# hauptplatine.net
KiCad netlist of a schematic drawn in EAGLE
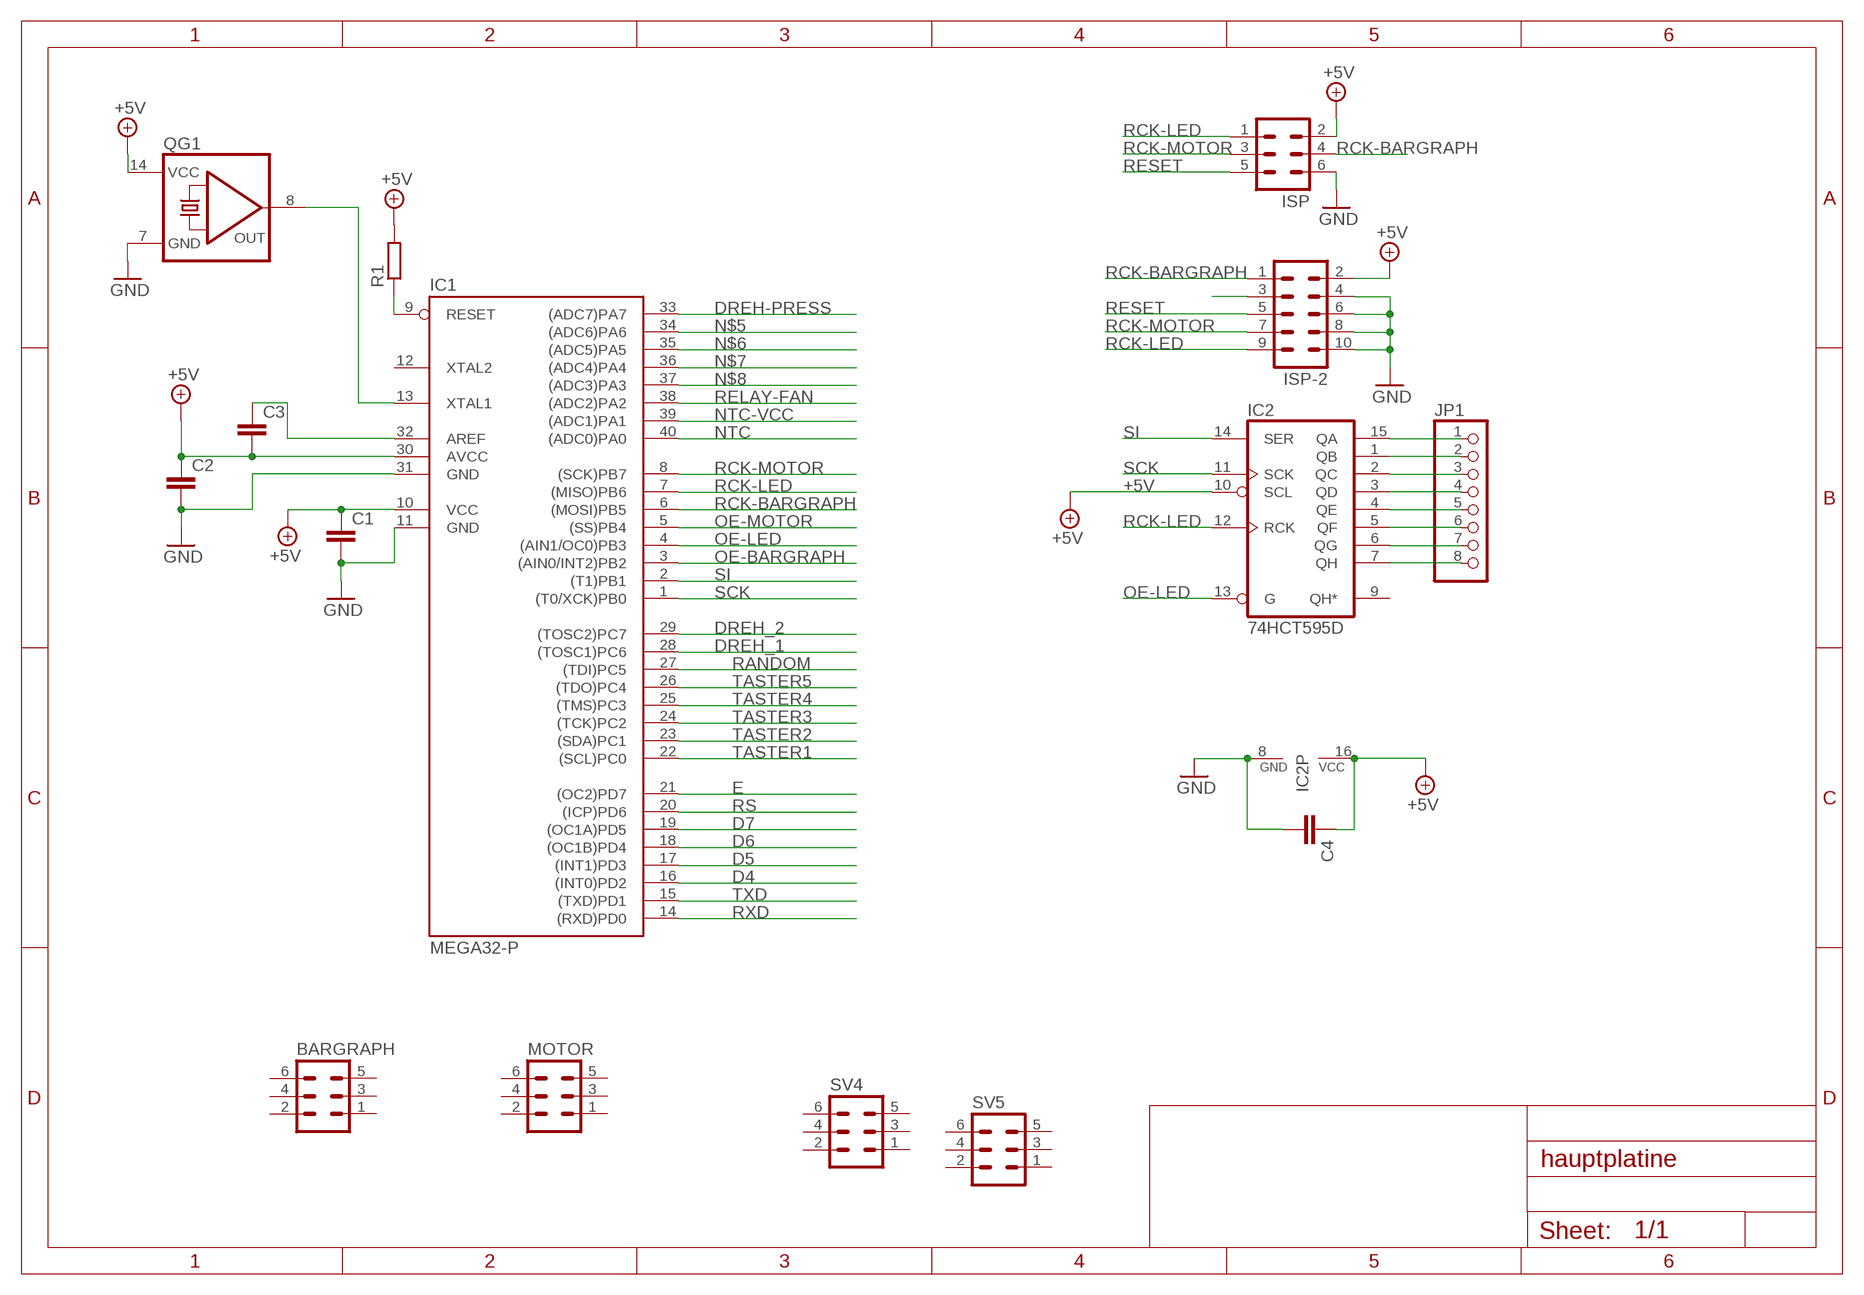
[diagram p0: schematic, sheet 1]

(export (version "E")
  (design (tool "Eeschema 10.0.6"))
  (components
    (comp (ref "BARGRAPH")
      (value "ML6")
      (footprint "eagle-import:ML6")
      (libsource (lib "eagle-import") (part "ML6"))
    )
    (comp (ref "C1")
      (value "C-EU025-025X050")
      (footprint "eagle-import:C025-025X050")
      (libsource (lib "eagle-import") (part "C-EU025-025X050"))
    )
    (comp (ref "C2")
      (value "C-EUC0805")
      (footprint "eagle-import:C0805")
      (libsource (lib "eagle-import") (part "C-EUC0805"))
    )
    (comp (ref "C3")
      (value "C-EUC0805")
      (footprint "eagle-import:C0805")
      (libsource (lib "eagle-import") (part "C-EUC0805"))
    )
    (comp (ref "C4")
      (value "C-EU025-025X050")
      (footprint "eagle-import:C025-025X050")
      (libsource (lib "eagle-import") (part "C-EU025-025X050"))
    )
    (comp (ref "IC1")
      (value "MEGA32-P")
      (footprint "eagle-import:DIL40")
      (fields (field (name "MPN") "ATMEGA32-16PU"))
      (libsource (lib "eagle-import") (part "MEGA32-P"))
    )
    (comp (ref "IC2")
      (value "74HCT595D")
      (footprint "eagle-import:SO16")
      (libsource (lib "eagle-import") (part "74595DHCT"))
    )
    (comp (ref "ISP")
      (value "ML6")
      (footprint "eagle-import:ML6")
      (libsource (lib "eagle-import") (part "ML6"))
    )
    (comp (ref "ISP-2")
      (value "ML10")
      (footprint "eagle-import:ML10")
      (libsource (lib "eagle-import") (part "ML10"))
    )
    (comp (ref "JP1")
      (value "PINHD-1X8")
      (footprint "eagle-import:1X08")
      (libsource (lib "eagle-import") (part "PINHD-1X8"))
    )
    (comp (ref "MOTOR")
      (value "ML6")
      (footprint "eagle-import:ML6")
      (libsource (lib "eagle-import") (part "ML6"))
    )
    (comp (ref "QG1")
      (value "QG5860")
      (footprint "eagle-import:DIL14S")
      (libsource (lib "eagle-import") (part "QG5860"))
    )
    (comp (ref "R1")
      (value "R-EU_0207/10")
      (footprint "eagle-import:0207_10")
      (libsource (lib "eagle-import") (part "R-EU_0207/10"))
    )
    (comp (ref "SV4")
      (value "ML6")
      (footprint "eagle-import:ML6")
      (libsource (lib "eagle-import") (part "ML6"))
    )
    (comp (ref "SV5")
      (value "ML6")
      (footprint "eagle-import:ML6")
      (libsource (lib "eagle-import") (part "ML6"))
    )
  )
  (nets
    (net (code "1") (name "+5V") (class "Default")
      (node (ref "C1") (pin "1") (pinfunction "1_1") (pintype "passive"))
      (node (ref "C2") (pin "1") (pinfunction "1_1") (pintype "passive"))
      (node (ref "C3") (pin "2") (pinfunction "2_2") (pintype "passive"))
      (node (ref "C4") (pin "1") (pinfunction "1_1") (pintype "passive"))
      (node (ref "IC1") (pin "10") (pinfunction "VCC_10") (pintype "power_in"))
      (node (ref "IC1") (pin "30") (pinfunction "AVCC_30") (pintype "power_in"))
      (node (ref "IC2") (pin "10") (pinfunction "SCL_10") (pintype "input"))
      (node (ref "IC2") (pin "16") (pinfunction "VCC_16") (pintype "power_in"))
      (node (ref "ISP") (pin "2") (pinfunction "2_2") (pintype "passive"))
      (node (ref "ISP-2") (pin "2") (pinfunction "2_2") (pintype "passive"))
      (node (ref "QG1") (pin "14") (pinfunction "VCC_14") (pintype "power_in"))
      (node (ref "R1") (pin "2") (pinfunction "2_2") (pintype "passive"))
    )
    (net (code "2") (name "/D4") (class "Default")
      (node (ref "IC1") (pin "16") (pinfunction "(INT0)PD2_16") (pintype "bidirectional"))
    )
    (net (code "3") (name "/D5") (class "Default")
      (node (ref "IC1") (pin "17") (pinfunction "(INT1)PD3_17") (pintype "bidirectional"))
    )
    (net (code "4") (name "/D6") (class "Default")
      (node (ref "IC1") (pin "18") (pinfunction "(OC1B)PD4_18") (pintype "bidirectional"))
    )
    (net (code "5") (name "/D7") (class "Default")
      (node (ref "IC1") (pin "19") (pinfunction "(OC1A)PD5_19") (pintype "bidirectional"))
    )
    (net (code "6") (name "/DREH-PRESS") (class "Default")
      (node (ref "IC1") (pin "33") (pinfunction "(ADC7)PA7_33") (pintype "bidirectional"))
    )
    (net (code "7") (name "/DREH_1") (class "Default")
      (node (ref "IC1") (pin "28") (pinfunction "(TOSC1)PC6_28") (pintype "bidirectional"))
    )
    (net (code "8") (name "/DREH_2") (class "Default")
      (node (ref "IC1") (pin "29") (pinfunction "(TOSC2)PC7_29") (pintype "bidirectional"))
    )
    (net (code "9") (name "/E") (class "Default")
      (node (ref "IC1") (pin "21") (pinfunction "(OC2)PD7_21") (pintype "bidirectional"))
    )
    (net (code "10") (name "/N$5") (class "Default")
      (node (ref "IC1") (pin "34") (pinfunction "(ADC6)PA6_34") (pintype "bidirectional"))
    )
    (net (code "11") (name "/N$6") (class "Default")
      (node (ref "IC1") (pin "35") (pinfunction "(ADC5)PA5_35") (pintype "bidirectional"))
    )
    (net (code "12") (name "/N$7") (class "Default")
      (node (ref "IC1") (pin "36") (pinfunction "(ADC4)PA4_36") (pintype "bidirectional"))
    )
    (net (code "13") (name "/N$8") (class "Default")
      (node (ref "IC1") (pin "37") (pinfunction "(ADC3)PA3_37") (pintype "bidirectional"))
    )
    (net (code "14") (name "/NTC") (class "Default")
      (node (ref "IC1") (pin "40") (pinfunction "(ADC0)PA0_40") (pintype "bidirectional"))
    )
    (net (code "15") (name "/NTC-VCC") (class "Default")
      (node (ref "IC1") (pin "39") (pinfunction "(ADC1)PA1_39") (pintype "bidirectional"))
    )
    (net (code "16") (name "/OE-BARGRAPH") (class "Default")
      (node (ref "IC1") (pin "3") (pinfunction "(AIN0/INT2)PB2_3") (pintype "bidirectional"))
    )
    (net (code "17") (name "/OE-LED") (class "Default")
      (node (ref "IC1") (pin "4") (pinfunction "(AIN1/OC0)PB3_4") (pintype "bidirectional"))
      (node (ref "IC2") (pin "13") (pinfunction "G_13") (pintype "input"))
    )
    (net (code "18") (name "/OE-MOTOR") (class "Default")
      (node (ref "IC1") (pin "5") (pinfunction "(SS)PB4_5") (pintype "bidirectional"))
    )
    (net (code "19") (name "/RANDOM") (class "Default")
      (node (ref "IC1") (pin "27") (pinfunction "(TDI)PC5_27") (pintype "bidirectional"))
    )
    (net (code "20") (name "/RCK-BARGRAPH") (class "Default")
      (node (ref "IC1") (pin "6") (pinfunction "(MOSI)PB5_6") (pintype "bidirectional"))
      (node (ref "ISP") (pin "4") (pinfunction "4_4") (pintype "passive"))
      (node (ref "ISP-2") (pin "1") (pinfunction "1_1") (pintype "passive"))
    )
    (net (code "21") (name "/RCK-LED") (class "Default")
      (node (ref "IC1") (pin "7") (pinfunction "(MISO)PB6_7") (pintype "bidirectional"))
      (node (ref "IC2") (pin "12") (pinfunction "RCK_12") (pintype "input"))
      (node (ref "ISP") (pin "1") (pinfunction "1_1") (pintype "passive"))
      (node (ref "ISP-2") (pin "9") (pinfunction "9_9") (pintype "passive"))
    )
    (net (code "22") (name "/RCK-MOTOR") (class "Default")
      (node (ref "IC1") (pin "8") (pinfunction "(SCK)PB7_8") (pintype "bidirectional"))
      (node (ref "ISP") (pin "3") (pinfunction "3_3") (pintype "passive"))
      (node (ref "ISP-2") (pin "7") (pinfunction "7_7") (pintype "passive"))
    )
    (net (code "23") (name "/RELAY-FAN") (class "Default")
      (node (ref "IC1") (pin "38") (pinfunction "(ADC2)PA2_38") (pintype "bidirectional"))
    )
    (net (code "24") (name "/RESET") (class "Default")
      (node (ref "IC1") (pin "9") (pinfunction "RESET_9") (pintype "input"))
      (node (ref "ISP") (pin "5") (pinfunction "5_5") (pintype "passive"))
      (node (ref "ISP-2") (pin "5") (pinfunction "5_5") (pintype "passive"))
      (node (ref "R1") (pin "1") (pinfunction "1_1") (pintype "passive"))
    )
    (net (code "25") (name "/RS") (class "Default")
      (node (ref "IC1") (pin "20") (pinfunction "(ICP)PD6_20") (pintype "bidirectional"))
    )
    (net (code "26") (name "/RXD") (class "Default")
      (node (ref "IC1") (pin "14") (pinfunction "(RXD)PD0_14") (pintype "bidirectional"))
    )
    (net (code "27") (name "/SCK") (class "Default")
      (node (ref "IC1") (pin "1") (pinfunction "(T0/XCK)PB0_1") (pintype "bidirectional"))
      (node (ref "IC2") (pin "11") (pinfunction "SCK_11") (pintype "input"))
    )
    (net (code "28") (name "/SI") (class "Default")
      (node (ref "IC1") (pin "2") (pinfunction "(T1)PB1_2") (pintype "bidirectional"))
      (node (ref "IC2") (pin "14") (pinfunction "SER_14") (pintype "input"))
    )
    (net (code "29") (name "/TASTER1") (class "Default")
      (node (ref "IC1") (pin "22") (pinfunction "(SCL)PC0_22") (pintype "bidirectional"))
    )
    (net (code "30") (name "/TASTER2") (class "Default")
      (node (ref "IC1") (pin "23") (pinfunction "(SDA)PC1_23") (pintype "bidirectional"))
    )
    (net (code "31") (name "/TASTER3") (class "Default")
      (node (ref "IC1") (pin "24") (pinfunction "(TCK)PC2_24") (pintype "bidirectional"))
    )
    (net (code "32") (name "/TASTER4") (class "Default")
      (node (ref "IC1") (pin "25") (pinfunction "(TMS)PC3_25") (pintype "bidirectional"))
    )
    (net (code "33") (name "/TASTER5") (class "Default")
      (node (ref "IC1") (pin "26") (pinfunction "(TDO)PC4_26") (pintype "bidirectional"))
    )
    (net (code "34") (name "/TXD") (class "Default")
      (node (ref "IC1") (pin "15") (pinfunction "(TXD)PD1_15") (pintype "bidirectional"))
    )
    (net (code "35") (name "GND") (class "Default")
      (node (ref "C1") (pin "2") (pinfunction "2_2") (pintype "passive"))
      (node (ref "C2") (pin "2") (pinfunction "2_2") (pintype "passive"))
      (node (ref "C4") (pin "2") (pinfunction "2_2") (pintype "passive"))
      (node (ref "IC1") (pin "11") (pinfunction "GND_11") (pintype "power_in"))
      (node (ref "IC1") (pin "31") (pinfunction "GND_31") (pintype "power_in"))
      (node (ref "IC2") (pin "8") (pinfunction "GND_8") (pintype "power_in"))
      (node (ref "ISP") (pin "6") (pinfunction "6_6") (pintype "passive"))
      (node (ref "ISP-2") (pin "10") (pinfunction "10_10") (pintype "passive"))
      (node (ref "ISP-2") (pin "4") (pinfunction "4_4") (pintype "passive"))
      (node (ref "ISP-2") (pin "6") (pinfunction "6_6") (pintype "passive"))
      (node (ref "ISP-2") (pin "8") (pinfunction "8_8") (pintype "passive"))
      (node (ref "QG1") (pin "7") (pinfunction "GND_7") (pintype "power_in"))
    )
    (net (code "36") (name "Net-(IC1-AREF)") (class "Default")
      (node (ref "C3") (pin "1") (pinfunction "1_1") (pintype "passive"))
      (node (ref "IC1") (pin "32") (pinfunction "AREF_32") (pintype "passive"))
    )
    (net (code "37") (name "Net-(IC1-XTAL1)") (class "Default")
      (node (ref "IC1") (pin "13") (pinfunction "XTAL1_13") (pintype "bidirectional"))
      (node (ref "QG1") (pin "8") (pinfunction "OUT_8") (pintype "output"))
    )
    (net (code "38") (name "Net-(IC2A-QA)") (class "Default")
      (node (ref "IC2") (pin "15") (pinfunction "QA_15") (pintype "tri_state"))
      (node (ref "JP1") (pin "1") (pinfunction "1_1") (pintype "passive"))
    )
    (net (code "39") (name "Net-(IC2A-QB)") (class "Default")
      (node (ref "IC2") (pin "1") (pinfunction "QB_1") (pintype "tri_state"))
      (node (ref "JP1") (pin "2") (pinfunction "2_2") (pintype "passive"))
    )
    (net (code "40") (name "Net-(IC2A-QC)") (class "Default")
      (node (ref "IC2") (pin "2") (pinfunction "QC_2") (pintype "tri_state"))
      (node (ref "JP1") (pin "3") (pinfunction "3_3") (pintype "passive"))
    )
    (net (code "41") (name "Net-(IC2A-QD)") (class "Default")
      (node (ref "IC2") (pin "3") (pinfunction "QD_3") (pintype "tri_state"))
      (node (ref "JP1") (pin "4") (pinfunction "4_4") (pintype "passive"))
    )
    (net (code "42") (name "Net-(IC2A-QE)") (class "Default")
      (node (ref "IC2") (pin "4") (pinfunction "QE_4") (pintype "tri_state"))
      (node (ref "JP1") (pin "5") (pinfunction "5_5") (pintype "passive"))
    )
    (net (code "43") (name "Net-(IC2A-QF)") (class "Default")
      (node (ref "IC2") (pin "5") (pinfunction "QF_5") (pintype "tri_state"))
      (node (ref "JP1") (pin "6") (pinfunction "6_6") (pintype "passive"))
    )
    (net (code "44") (name "Net-(IC2A-QG)") (class "Default")
      (node (ref "IC2") (pin "6") (pinfunction "QG_6") (pintype "tri_state"))
      (node (ref "JP1") (pin "7") (pinfunction "7_7") (pintype "passive"))
    )
    (net (code "45") (name "Net-(IC2A-QH)") (class "Default")
      (node (ref "IC2") (pin "7") (pinfunction "QH_7") (pintype "tri_state"))
      (node (ref "JP1") (pin "8") (pinfunction "8_8") (pintype "passive"))
    )
    (net (code "46") (name "unconnected-(BARGRAPH-Pad1)") (class "Default")
      (node (ref "BARGRAPH") (pin "1") (pinfunction "1_1") (pintype "passive"))
    )
    (net (code "47") (name "unconnected-(BARGRAPH-Pad2)") (class "Default")
      (node (ref "BARGRAPH") (pin "2") (pinfunction "2_2") (pintype "passive"))
    )
    (net (code "48") (name "unconnected-(BARGRAPH-Pad3)") (class "Default")
      (node (ref "BARGRAPH") (pin "3") (pinfunction "3_3") (pintype "passive"))
    )
    (net (code "49") (name "unconnected-(BARGRAPH-Pad4)") (class "Default")
      (node (ref "BARGRAPH") (pin "4") (pinfunction "4_4") (pintype "passive"))
    )
    (net (code "50") (name "unconnected-(BARGRAPH-Pad5)") (class "Default")
      (node (ref "BARGRAPH") (pin "5") (pinfunction "5_5") (pintype "passive"))
    )
    (net (code "51") (name "unconnected-(BARGRAPH-Pad6)") (class "Default")
      (node (ref "BARGRAPH") (pin "6") (pinfunction "6_6") (pintype "passive"))
    )
    (net (code "52") (name "unconnected-(IC1-XTAL2-Pad12)") (class "Default")
      (node (ref "IC1") (pin "12") (pinfunction "XTAL2_12") (pintype "bidirectional"))
    )
    (net (code "53") (name "unconnected-(IC2A-QH*-Pad9)") (class "Default")
      (node (ref "IC2") (pin "9") (pinfunction "QH*_9") (pintype "tri_state"))
    )
    (net (code "54") (name "unconnected-(ISP-2-Pad3)") (class "Default")
      (node (ref "ISP-2") (pin "3") (pinfunction "3_3") (pintype "passive"))
    )
    (net (code "55") (name "unconnected-(MOTOR-Pad1)") (class "Default")
      (node (ref "MOTOR") (pin "1") (pinfunction "1_1") (pintype "passive"))
    )
    (net (code "56") (name "unconnected-(MOTOR-Pad2)") (class "Default")
      (node (ref "MOTOR") (pin "2") (pinfunction "2_2") (pintype "passive"))
    )
    (net (code "57") (name "unconnected-(MOTOR-Pad3)") (class "Default")
      (node (ref "MOTOR") (pin "3") (pinfunction "3_3") (pintype "passive"))
    )
    (net (code "58") (name "unconnected-(MOTOR-Pad4)") (class "Default")
      (node (ref "MOTOR") (pin "4") (pinfunction "4_4") (pintype "passive"))
    )
    (net (code "59") (name "unconnected-(MOTOR-Pad5)") (class "Default")
      (node (ref "MOTOR") (pin "5") (pinfunction "5_5") (pintype "passive"))
    )
    (net (code "60") (name "unconnected-(MOTOR-Pad6)") (class "Default")
      (node (ref "MOTOR") (pin "6") (pinfunction "6_6") (pintype "passive"))
    )
    (net (code "61") (name "unconnected-(SV4-Pad1)") (class "Default")
      (node (ref "SV4") (pin "1") (pinfunction "1_1") (pintype "passive"))
    )
    (net (code "62") (name "unconnected-(SV4-Pad2)") (class "Default")
      (node (ref "SV4") (pin "2") (pinfunction "2_2") (pintype "passive"))
    )
    (net (code "63") (name "unconnected-(SV4-Pad3)") (class "Default")
      (node (ref "SV4") (pin "3") (pinfunction "3_3") (pintype "passive"))
    )
    (net (code "64") (name "unconnected-(SV4-Pad4)") (class "Default")
      (node (ref "SV4") (pin "4") (pinfunction "4_4") (pintype "passive"))
    )
    (net (code "65") (name "unconnected-(SV4-Pad5)") (class "Default")
      (node (ref "SV4") (pin "5") (pinfunction "5_5") (pintype "passive"))
    )
    (net (code "66") (name "unconnected-(SV4-Pad6)") (class "Default")
      (node (ref "SV4") (pin "6") (pinfunction "6_6") (pintype "passive"))
    )
    (net (code "67") (name "unconnected-(SV5-Pad1)") (class "Default")
      (node (ref "SV5") (pin "1") (pinfunction "1_1") (pintype "passive"))
    )
    (net (code "68") (name "unconnected-(SV5-Pad2)") (class "Default")
      (node (ref "SV5") (pin "2") (pinfunction "2_2") (pintype "passive"))
    )
    (net (code "69") (name "unconnected-(SV5-Pad3)") (class "Default")
      (node (ref "SV5") (pin "3") (pinfunction "3_3") (pintype "passive"))
    )
    (net (code "70") (name "unconnected-(SV5-Pad4)") (class "Default")
      (node (ref "SV5") (pin "4") (pinfunction "4_4") (pintype "passive"))
    )
    (net (code "71") (name "unconnected-(SV5-Pad5)") (class "Default")
      (node (ref "SV5") (pin "5") (pinfunction "5_5") (pintype "passive"))
    )
    (net (code "72") (name "unconnected-(SV5-Pad6)") (class "Default")
      (node (ref "SV5") (pin "6") (pinfunction "6_6") (pintype "passive"))
    )
  )
)
